# SkateMate_Receiver.net
KiCad netlist of a schematic drawn in EAGLE
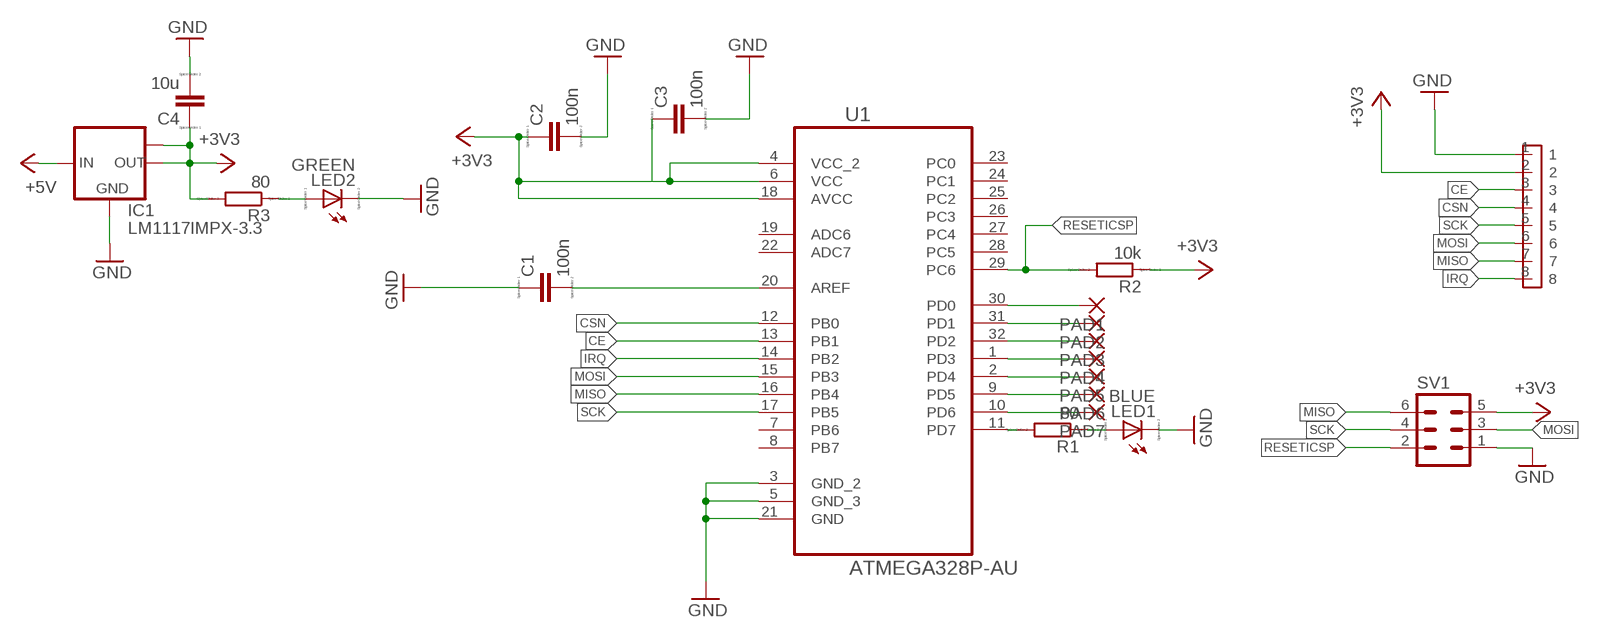
[diagram p0: schematic, sheet 1]

(export (version "E")
  (design (tool "Eeschema 10.0.6"))
  (components
    (comp (ref "C1")
      (value "100n")
      (footprint "eagle-import:C0603")
      (libsource (lib "eagle-import") (part "CC0603"))
    )
    (comp (ref "C2")
      (value "100n")
      (footprint "eagle-import:C0603")
      (libsource (lib "eagle-import") (part "CC0603"))
    )
    (comp (ref "C3")
      (value "100n")
      (footprint "eagle-import:C0603")
      (libsource (lib "eagle-import") (part "CC0603"))
    )
    (comp (ref "C4")
      (value "10u")
      (footprint "eagle-import:C0603")
      (libsource (lib "eagle-import") (part "CC0603"))
    )
    (comp (ref "IC1")
      (value "LM1117IMPX-3.3")
      (footprint "eagle-import:SOT223")
      (libsource (lib "eagle-import") (part "LM1117IMPX-3.3"))
    )
    (comp (ref "LED1")
      (value "BLUE")
      (footprint "eagle-import:LED_SML0603")
      (libsource (lib "eagle-import") (part "LED_ESML0603"))
    )
    (comp (ref "LED2")
      (value "GREEN")
      (footprint "eagle-import:LED_SML0603")
      (libsource (lib "eagle-import") (part "LED_ESML0603"))
    )
    (comp (ref "PAD1")
      (value "1,6/0,8")
      (footprint "eagle-import:1,6_0,8")
      (libsource (lib "eagle-import") (part "1,6/0,8"))
    )
    (comp (ref "PAD2")
      (value "1,6/0,8")
      (footprint "eagle-import:1,6_0,8")
      (libsource (lib "eagle-import") (part "1,6/0,8"))
    )
    (comp (ref "PAD3")
      (value "1,6/0,8")
      (footprint "eagle-import:1,6_0,8")
      (libsource (lib "eagle-import") (part "1,6/0,8"))
    )
    (comp (ref "PAD4")
      (value "1,6/0,8")
      (footprint "eagle-import:1,6_0,8")
      (libsource (lib "eagle-import") (part "1,6/0,8"))
    )
    (comp (ref "PAD5")
      (value "1,6/0,8")
      (footprint "eagle-import:1,6_0,8")
      (libsource (lib "eagle-import") (part "1,6/0,8"))
    )
    (comp (ref "PAD6")
      (value "1,6/0,8")
      (footprint "eagle-import:1,6_0,8")
      (libsource (lib "eagle-import") (part "1,6/0,8"))
    )
    (comp (ref "PAD7")
      (value "1,6/0,8")
      (footprint "eagle-import:1,6_0,8")
      (libsource (lib "eagle-import") (part "1,6/0,8"))
    )
    (comp (ref "R1")
      (value "80")
      (footprint "eagle-import:R0603")
      (libsource (lib "eagle-import") (part "RR0603"))
    )
    (comp (ref "R2")
      (value "10k")
      (footprint "eagle-import:R0603")
      (libsource (lib "eagle-import") (part "RR0603"))
    )
    (comp (ref "R3")
      (value "80")
      (footprint "eagle-import:R0603")
      (libsource (lib "eagle-import") (part "RR0603"))
    )
    (comp (ref "SV1")
      (value "MA03-2")
      (footprint "eagle-import:MA03-2")
      (libsource (lib "eagle-import") (part "MA03-2"))
    )
    (comp (ref "U$1")
      (value "HEADER1,27")
      (footprint "eagle-import:HEADER1,27")
      (libsource (lib "eagle-import") (part "HEADER1,27"))
    )
    (comp (ref "U1")
      (value "ATMEGA328P-AU")
      (footprint "eagle-import:QFP80P900X900X120-32N")
      (libsource (lib "eagle-import") (part "ATMEGA328P-AU"))
    )
  )
  (nets
    (net (code "1") (name "+3V3") (class "Default")
      (node (ref "C2") (pin "1") (pinfunction "1_1") (pintype "passive"))
      (node (ref "C3") (pin "1") (pinfunction "1_1") (pintype "passive"))
      (node (ref "C4") (pin "1") (pinfunction "1_1") (pintype "passive"))
      (node (ref "IC1") (pin "2") (pinfunction "OUT_2") (pintype "passive"))
      (node (ref "IC1") (pin "TAB") (pinfunction "OUT1_TAB") (pintype "passive"))
      (node (ref "R2") (pin "1") (pinfunction "1_1") (pintype "passive"))
      (node (ref "R3") (pin "2") (pinfunction "2_2") (pintype "passive"))
      (node (ref "SV1") (pin "5") (pinfunction "5_5") (pintype "passive"))
      (node (ref "U$1") (pin "2") (pinfunction "2_2") (pintype "bidirectional"))
      (node (ref "U1") (pin "18") (pinfunction "AVCC_18") (pintype "power_in"))
      (node (ref "U1") (pin "4") (pinfunction "VCC_2_4") (pintype "power_in"))
      (node (ref "U1") (pin "6") (pinfunction "VCC_6") (pintype "power_in"))
    )
    (net (code "2") (name "+5V") (class "Default")
      (node (ref "IC1") (pin "3") (pinfunction "IN_3") (pintype "input"))
    )
    (net (code "3") (name "CE") (class "Default")
      (node (ref "U$1") (pin "3") (pinfunction "3_3") (pintype "bidirectional"))
      (node (ref "U1") (pin "13") (pinfunction "PB1_13") (pintype "bidirectional"))
    )
    (net (code "4") (name "CSN") (class "Default")
      (node (ref "U$1") (pin "4") (pinfunction "4_4") (pintype "bidirectional"))
      (node (ref "U1") (pin "12") (pinfunction "PB0_12") (pintype "bidirectional"))
    )
    (net (code "5") (name "GND") (class "Default")
      (node (ref "C1") (pin "1") (pinfunction "1_1") (pintype "passive"))
      (node (ref "C2") (pin "2") (pinfunction "2_2") (pintype "passive"))
      (node (ref "C3") (pin "2") (pinfunction "2_2") (pintype "passive"))
      (node (ref "C4") (pin "2") (pinfunction "2_2") (pintype "passive"))
      (node (ref "IC1") (pin "1") (pinfunction "GND_1") (pintype "input"))
      (node (ref "LED1") (pin "C") (pinfunction "C_C") (pintype "passive"))
      (node (ref "LED2") (pin "C") (pinfunction "C_C") (pintype "passive"))
      (node (ref "SV1") (pin "1") (pinfunction "1_1") (pintype "passive"))
      (node (ref "U$1") (pin "1") (pinfunction "1_1") (pintype "bidirectional"))
      (node (ref "U1") (pin "21") (pinfunction "GND_21") (pintype "passive"))
      (node (ref "U1") (pin "3") (pinfunction "GND_2_3") (pintype "passive"))
      (node (ref "U1") (pin "5") (pinfunction "GND_3_5") (pintype "passive"))
    )
    (net (code "6") (name "IRQ") (class "Default")
      (node (ref "U$1") (pin "8") (pinfunction "8_8") (pintype "bidirectional"))
      (node (ref "U1") (pin "14") (pinfunction "PB2_14") (pintype "bidirectional"))
    )
    (net (code "7") (name "MISO") (class "Default")
      (node (ref "SV1") (pin "6") (pinfunction "6_6") (pintype "passive"))
      (node (ref "U$1") (pin "7") (pinfunction "7_7") (pintype "bidirectional"))
      (node (ref "U1") (pin "16") (pinfunction "PB4_16") (pintype "bidirectional"))
    )
    (net (code "8") (name "MOSI") (class "Default")
      (node (ref "SV1") (pin "3") (pinfunction "3_3") (pintype "passive"))
      (node (ref "U$1") (pin "6") (pinfunction "6_6") (pintype "bidirectional"))
      (node (ref "U1") (pin "15") (pinfunction "PB3_15") (pintype "bidirectional"))
    )
    (net (code "9") (name "Net-(LED1-PadA)") (class "Default")
      (node (ref "LED1") (pin "A") (pinfunction "A_A") (pintype "passive"))
      (node (ref "R1") (pin "1") (pinfunction "1_1") (pintype "passive"))
    )
    (net (code "10") (name "Net-(LED2-PadA)") (class "Default")
      (node (ref "LED2") (pin "A") (pinfunction "A_A") (pintype "passive"))
      (node (ref "R3") (pin "1") (pinfunction "1_1") (pintype "passive"))
    )
    (net (code "11") (name "Net-(PAD1-P)") (class "Default")
      (node (ref "PAD1") (pin "1") (pinfunction "P_1") (pintype "passive"))
      (node (ref "U1") (pin "30") (pinfunction "PD0_30") (pintype "bidirectional"))
    )
    (net (code "12") (name "Net-(PAD2-P)") (class "Default")
      (node (ref "PAD2") (pin "1") (pinfunction "P_1") (pintype "passive"))
      (node (ref "U1") (pin "31") (pinfunction "PD1_31") (pintype "bidirectional"))
    )
    (net (code "13") (name "Net-(PAD3-P)") (class "Default")
      (node (ref "PAD3") (pin "1") (pinfunction "P_1") (pintype "passive"))
      (node (ref "U1") (pin "32") (pinfunction "PD2_32") (pintype "bidirectional"))
    )
    (net (code "14") (name "Net-(PAD4-P)") (class "Default")
      (node (ref "PAD4") (pin "1") (pinfunction "P_1") (pintype "passive"))
      (node (ref "U1") (pin "1") (pinfunction "PD3_1") (pintype "bidirectional"))
    )
    (net (code "15") (name "Net-(PAD5-P)") (class "Default")
      (node (ref "PAD5") (pin "1") (pinfunction "P_1") (pintype "passive"))
      (node (ref "U1") (pin "2") (pinfunction "PD4_2") (pintype "bidirectional"))
    )
    (net (code "16") (name "Net-(PAD6-P)") (class "Default")
      (node (ref "PAD6") (pin "1") (pinfunction "P_1") (pintype "passive"))
      (node (ref "U1") (pin "9") (pinfunction "PD5_9") (pintype "bidirectional"))
    )
    (net (code "17") (name "Net-(PAD7-P)") (class "Default")
      (node (ref "PAD7") (pin "1") (pinfunction "P_1") (pintype "passive"))
      (node (ref "U1") (pin "10") (pinfunction "PD6_10") (pintype "bidirectional"))
    )
    (net (code "18") (name "Net-(U1-AREF)") (class "Default")
      (node (ref "C1") (pin "2") (pinfunction "2_2") (pintype "passive"))
      (node (ref "U1") (pin "20") (pinfunction "AREF_20") (pintype "input"))
    )
    (net (code "19") (name "Net-(U1-PD7)") (class "Default")
      (node (ref "R1") (pin "2") (pinfunction "2_2") (pintype "passive"))
      (node (ref "U1") (pin "11") (pinfunction "PD7_11") (pintype "bidirectional"))
    )
    (net (code "20") (name "RESETICSP") (class "Default")
      (node (ref "R2") (pin "2") (pinfunction "2_2") (pintype "passive"))
      (node (ref "SV1") (pin "2") (pinfunction "2_2") (pintype "passive"))
      (node (ref "U1") (pin "29") (pinfunction "PC6_29") (pintype "bidirectional"))
    )
    (net (code "21") (name "SCK") (class "Default")
      (node (ref "SV1") (pin "4") (pinfunction "4_4") (pintype "passive"))
      (node (ref "U$1") (pin "5") (pinfunction "5_5") (pintype "bidirectional"))
      (node (ref "U1") (pin "17") (pinfunction "PB5_17") (pintype "bidirectional"))
    )
    (net (code "22") (name "unconnected-(U1-ADC6-Pad19)") (class "Default")
      (node (ref "U1") (pin "19") (pinfunction "ADC6_19") (pintype "input"))
    )
    (net (code "23") (name "unconnected-(U1-ADC7-Pad22)") (class "Default")
      (node (ref "U1") (pin "22") (pinfunction "ADC7_22") (pintype "input"))
    )
    (net (code "24") (name "unconnected-(U1-PB6-Pad7)") (class "Default")
      (node (ref "U1") (pin "7") (pinfunction "PB6_7") (pintype "bidirectional"))
    )
    (net (code "25") (name "unconnected-(U1-PB7-Pad8)") (class "Default")
      (node (ref "U1") (pin "8") (pinfunction "PB7_8") (pintype "bidirectional"))
    )
    (net (code "26") (name "unconnected-(U1-PC0-Pad23)") (class "Default")
      (node (ref "U1") (pin "23") (pinfunction "PC0_23") (pintype "bidirectional"))
    )
    (net (code "27") (name "unconnected-(U1-PC1-Pad24)") (class "Default")
      (node (ref "U1") (pin "24") (pinfunction "PC1_24") (pintype "bidirectional"))
    )
    (net (code "28") (name "unconnected-(U1-PC2-Pad25)") (class "Default")
      (node (ref "U1") (pin "25") (pinfunction "PC2_25") (pintype "bidirectional"))
    )
    (net (code "29") (name "unconnected-(U1-PC3-Pad26)") (class "Default")
      (node (ref "U1") (pin "26") (pinfunction "PC3_26") (pintype "bidirectional"))
    )
    (net (code "30") (name "unconnected-(U1-PC4-Pad27)") (class "Default")
      (node (ref "U1") (pin "27") (pinfunction "PC4_27") (pintype "bidirectional"))
    )
    (net (code "31") (name "unconnected-(U1-PC5-Pad28)") (class "Default")
      (node (ref "U1") (pin "28") (pinfunction "PC5_28") (pintype "bidirectional"))
    )
  )
)
